# moire_v2.net
KiCad netlist of a schematic drawn in EAGLE
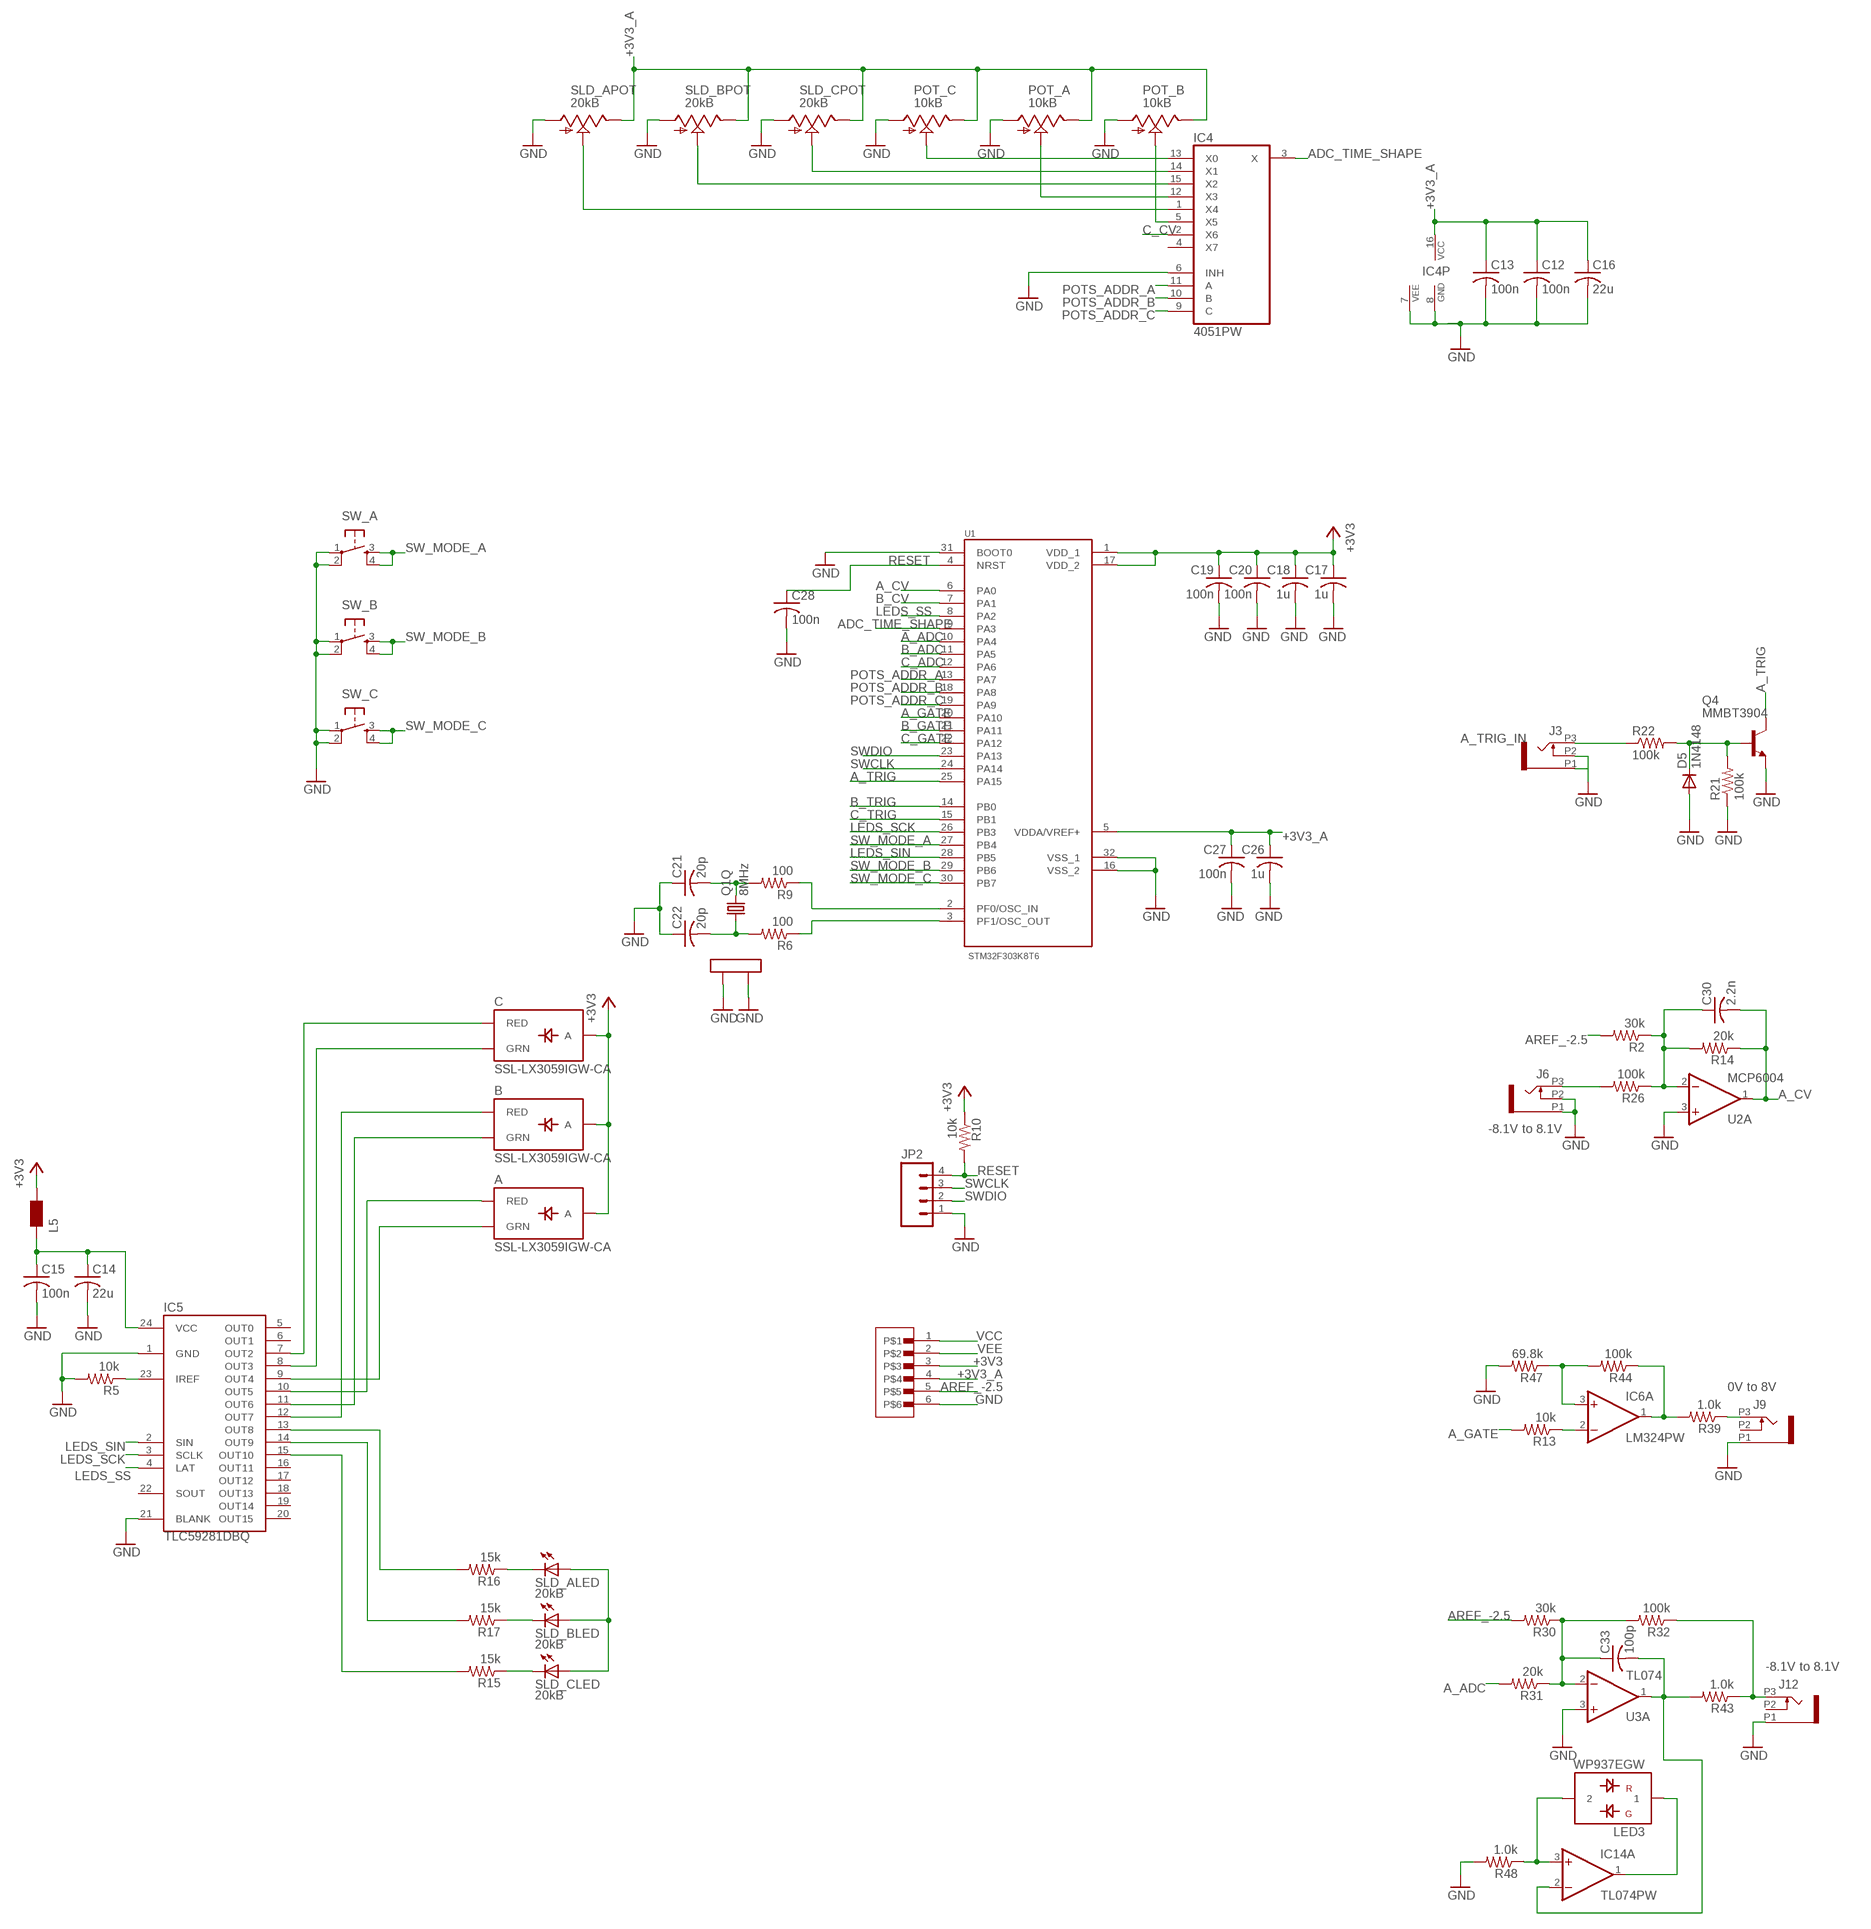
[diagram p0: schematic, sheet 1, part 1 of 2]
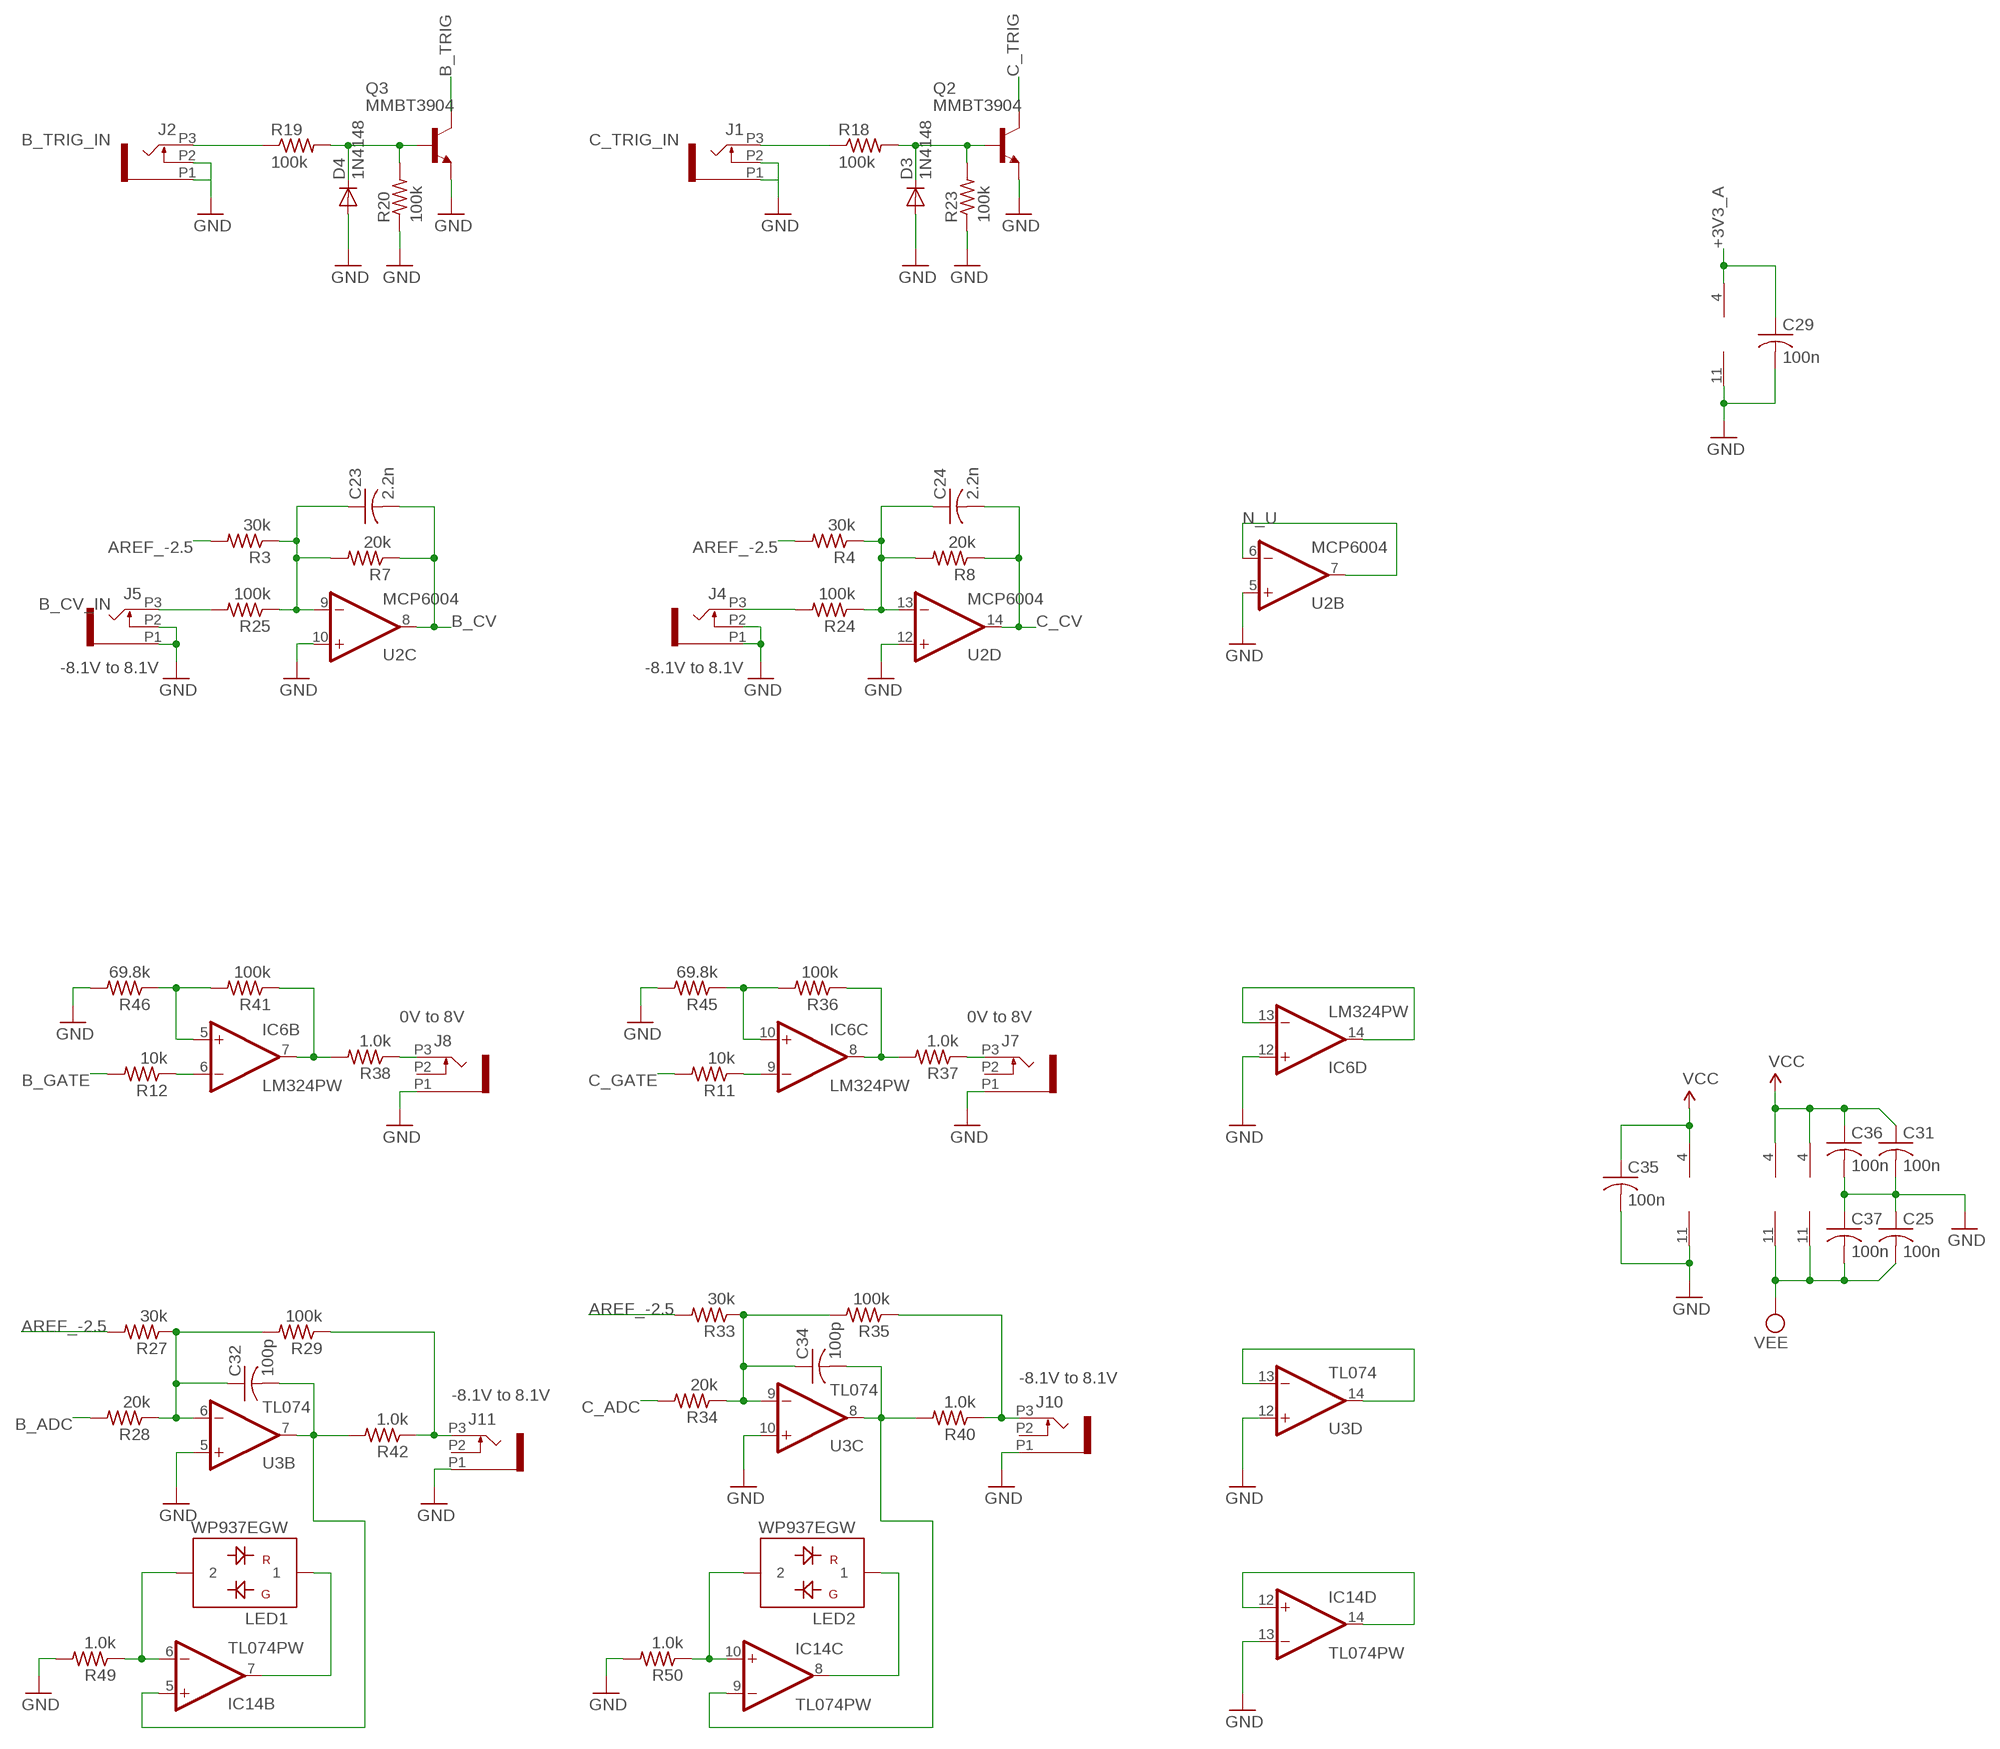
[diagram p1: schematic, sheet 1, part 2 of 2]
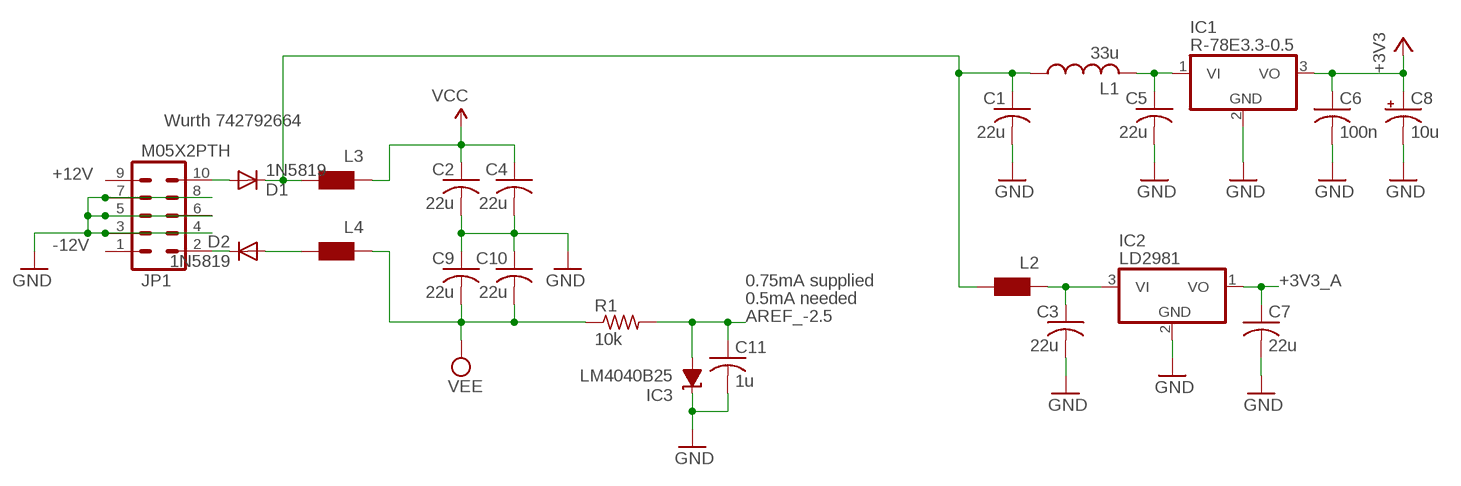
[diagram p2: schematic, sheet 2]

(export (version "E")
  (design (tool "Eeschema 10.0.6"))
  (components
    (comp (ref "A")
      (value "SSL-LX3059IGW-CA")
      (footprint "eagle-import:LED-BICOLOR-THROUGHHOLE-LUMEX")
      (libsource (lib "eagle-import") (part "LED-BICOLOR-THROUGHHOLE-CA"))
    )
    (comp (ref "B")
      (value "SSL-LX3059IGW-CA")
      (footprint "eagle-import:LED-BICOLOR-THROUGHHOLE-LUMEX")
      (libsource (lib "eagle-import") (part "LED-BICOLOR-THROUGHHOLE-CA"))
    )
    (comp (ref "C")
      (value "SSL-LX3059IGW-CA")
      (footprint "eagle-import:LED-BICOLOR-THROUGHHOLE-LUMEX")
      (libsource (lib "eagle-import") (part "LED-BICOLOR-THROUGHHOLE-CA"))
    )
    (comp (ref "C12")
      (value "100n")
      (footprint "eagle-import:RCL_C0603")
      (libsource (lib "eagle-import") (part "RCL_C-USC0603"))
    )
    (comp (ref "C13")
      (value "100n")
      (footprint "eagle-import:RCL_C0603")
      (libsource (lib "eagle-import") (part "RCL_C-USC0603"))
    )
    (comp (ref "C14")
      (value "22u")
      (footprint "eagle-import:RCL_C1206")
      (libsource (lib "eagle-import") (part "RCL_C-USC1206"))
    )
    (comp (ref "C15")
      (value "100n")
      (footprint "eagle-import:RCL_C0603")
      (libsource (lib "eagle-import") (part "RCL_C-USC0603"))
    )
    (comp (ref "C16")
      (value "22u")
      (footprint "eagle-import:RCL_C1206")
      (libsource (lib "eagle-import") (part "RCL_C-USC1206"))
    )
    (comp (ref "C17")
      (value "1u")
      (footprint "eagle-import:RCL_C0603")
      (libsource (lib "eagle-import") (part "RCL_C-USC0603"))
    )
    (comp (ref "C18")
      (value "1u")
      (footprint "eagle-import:RCL_C0603")
      (libsource (lib "eagle-import") (part "RCL_C-USC0603"))
    )
    (comp (ref "C19")
      (value "100n")
      (footprint "eagle-import:RCL_C0603")
      (libsource (lib "eagle-import") (part "RCL_C-USC0603"))
    )
    (comp (ref "C20")
      (value "100n")
      (footprint "eagle-import:RCL_C0603")
      (libsource (lib "eagle-import") (part "RCL_C-USC0603"))
    )
    (comp (ref "C21")
      (value "20p")
      (footprint "eagle-import:RCL_C0603")
      (libsource (lib "eagle-import") (part "RCL_C-USC0603"))
    )
    (comp (ref "C22")
      (value "20p")
      (footprint "eagle-import:RCL_C0603")
      (libsource (lib "eagle-import") (part "RCL_C-USC0603"))
    )
    (comp (ref "C23")
      (value "2.2n")
      (footprint "eagle-import:RCL_C0603")
      (libsource (lib "eagle-import") (part "RCL_C-USC0603"))
    )
    (comp (ref "C24")
      (value "2.2n")
      (footprint "eagle-import:RCL_C0603")
      (libsource (lib "eagle-import") (part "RCL_C-USC0603"))
    )
    (comp (ref "C25")
      (value "100n")
      (footprint "eagle-import:RCL_C0603")
      (libsource (lib "eagle-import") (part "RCL_C-USC0603"))
    )
    (comp (ref "C26")
      (value "1u")
      (footprint "eagle-import:RCL_C0603")
      (libsource (lib "eagle-import") (part "RCL_C-USC0603"))
    )
    (comp (ref "C27")
      (value "100n")
      (footprint "eagle-import:RCL_C0603")
      (libsource (lib "eagle-import") (part "RCL_C-USC0603"))
    )
    (comp (ref "C28")
      (value "100n")
      (footprint "eagle-import:RCL_C0603")
      (libsource (lib "eagle-import") (part "RCL_C-USC0603"))
    )
    (comp (ref "C29")
      (value "100n")
      (footprint "eagle-import:RCL_C0603")
      (libsource (lib "eagle-import") (part "RCL_C-USC0603"))
    )
    (comp (ref "C30")
      (value "2.2n")
      (footprint "eagle-import:RCL_C0603")
      (libsource (lib "eagle-import") (part "RCL_C-USC0603"))
    )
    (comp (ref "C31")
      (value "100n")
      (footprint "eagle-import:RCL_C0603")
      (libsource (lib "eagle-import") (part "RCL_C-USC0603"))
    )
    (comp (ref "C32")
      (value "100p")
      (footprint "eagle-import:RCL_C0603")
      (libsource (lib "eagle-import") (part "RCL_C-USC0603"))
    )
    (comp (ref "C33")
      (value "100p")
      (footprint "eagle-import:RCL_C0603")
      (libsource (lib "eagle-import") (part "RCL_C-USC0603"))
    )
    (comp (ref "C34")
      (value "100p")
      (footprint "eagle-import:RCL_C0603")
      (libsource (lib "eagle-import") (part "RCL_C-USC0603"))
    )
    (comp (ref "C35")
      (value "100n")
      (footprint "eagle-import:RCL_C0603")
      (libsource (lib "eagle-import") (part "RCL_C-USC0603"))
    )
    (comp (ref "C36")
      (value "100n")
      (footprint "eagle-import:RCL_C0603")
      (libsource (lib "eagle-import") (part "RCL_C-USC0603"))
    )
    (comp (ref "C37")
      (value "100n")
      (footprint "eagle-import:RCL_C0603")
      (libsource (lib "eagle-import") (part "RCL_C-USC0603"))
    )
    (comp (ref "D3")
      (value "1N4148")
      (footprint "eagle-import:DIODE_SOD523")
      (libsource (lib "eagle-import") (part "DIODE_DIODE-SOD523"))
    )
    (comp (ref "D4")
      (value "1N4148")
      (footprint "eagle-import:DIODE_SOD523")
      (libsource (lib "eagle-import") (part "DIODE_DIODE-SOD523"))
    )
    (comp (ref "D5")
      (value "1N4148")
      (footprint "eagle-import:DIODE_SOD523")
      (libsource (lib "eagle-import") (part "DIODE_DIODE-SOD523"))
    )
    (comp (ref "IC4")
      (value "4051PW")
      (footprint "eagle-import:TSSOP16_065")
      (libsource (lib "eagle-import") (part "4051PW"))
    )
    (comp (ref "IC5")
      (value "TLC59281DBQ")
      (footprint "eagle-import:TSSOP24_0635")
      (libsource (lib "eagle-import") (part "TLC59281DBQ"))
    )
    (comp (ref "IC6")
      (value "LM324PW")
      (footprint "eagle-import:TSSOP14_065")
      (libsource (lib "eagle-import") (part "og-linear_TL074PW"))
    )
    (comp (ref "IC14")
      (value "TL074PW")
      (footprint "eagle-import:TSSOP14_065")
      (libsource (lib "eagle-import") (part "TL074PW"))
    )
    (comp (ref "J1")
      (value "PJ301_THONKICONN6")
      (footprint "eagle-import:WQP_PJ_301M6")
      (libsource (lib "eagle-import") (part "PJ301_THONKICONN6"))
    )
    (comp (ref "J2")
      (value "PJ301_THONKICONN6")
      (footprint "eagle-import:WQP_PJ_301M6")
      (libsource (lib "eagle-import") (part "PJ301_THONKICONN6"))
    )
    (comp (ref "J3")
      (value "PJ301_THONKICONN6")
      (footprint "eagle-import:WQP_PJ_301M6")
      (libsource (lib "eagle-import") (part "PJ301_THONKICONN6"))
    )
    (comp (ref "J4")
      (value "PJ301_THONKICONN6")
      (footprint "eagle-import:WQP_PJ_301M6")
      (libsource (lib "eagle-import") (part "PJ301_THONKICONN6"))
    )
    (comp (ref "J5")
      (value "PJ301_THONKICONN6")
      (footprint "eagle-import:WQP_PJ_301M6")
      (libsource (lib "eagle-import") (part "PJ301_THONKICONN6"))
    )
    (comp (ref "J6")
      (value "PJ301_THONKICONN6")
      (footprint "eagle-import:WQP_PJ_301M6")
      (libsource (lib "eagle-import") (part "PJ301_THONKICONN6"))
    )
    (comp (ref "J7")
      (value "PJ301_THONKICONN6")
      (footprint "eagle-import:WQP_PJ_301M6")
      (libsource (lib "eagle-import") (part "PJ301_THONKICONN6"))
    )
    (comp (ref "J8")
      (value "PJ301_THONKICONN6")
      (footprint "eagle-import:WQP_PJ_301M6")
      (libsource (lib "eagle-import") (part "PJ301_THONKICONN6"))
    )
    (comp (ref "J9")
      (value "PJ301_THONKICONN6")
      (footprint "eagle-import:WQP_PJ_301M6")
      (libsource (lib "eagle-import") (part "PJ301_THONKICONN6"))
    )
    (comp (ref "J10")
      (value "PJ301_THONKICONN6")
      (footprint "eagle-import:WQP_PJ_301M6")
      (libsource (lib "eagle-import") (part "PJ301_THONKICONN6"))
    )
    (comp (ref "J11")
      (value "PJ301_THONKICONN6")
      (footprint "eagle-import:WQP_PJ_301M6")
      (libsource (lib "eagle-import") (part "PJ301_THONKICONN6"))
    )
    (comp (ref "J12")
      (value "PJ301_THONKICONN6")
      (footprint "eagle-import:WQP_PJ_301M6")
      (libsource (lib "eagle-import") (part "PJ301_THONKICONN6"))
    )
    (comp (ref "JP2")
      (value "M04PTH")
      (footprint "eagle-import:1X04")
      (libsource (lib "eagle-import") (part "M04PTH"))
    )
    (comp (ref "L5")
      (value "WE-CBF_0603")
      (footprint "eagle-import:0603")
      (libsource (lib "eagle-import") (part "WE-CBF_0603"))
    )
    (comp (ref "LED1")
      (value "WP937EGW")
      (footprint "eagle-import:LED3MM")
      (libsource (lib "eagle-import") (part "LED-BICOLOR-SHARED-THROUGHHOLE"))
    )
    (comp (ref "LED2")
      (value "WP937EGW")
      (footprint "eagle-import:LED3MM")
      (libsource (lib "eagle-import") (part "LED-BICOLOR-SHARED-THROUGHHOLE"))
    )
    (comp (ref "LED3")
      (value "WP937EGW")
      (footprint "eagle-import:LED3MM")
      (libsource (lib "eagle-import") (part "LED-BICOLOR-SHARED-THROUGHHOLE"))
    )
    (comp (ref "POT_A")
      (value "10kB")
      (footprint "eagle-import:ALPS_POT_VERTICAL")
      (libsource (lib "eagle-import") (part "POT_USVERTICAL"))
    )
    (comp (ref "POT_B")
      (value "10kB")
      (footprint "eagle-import:ALPS_POT_VERTICAL")
      (libsource (lib "eagle-import") (part "POT_USVERTICAL"))
    )
    (comp (ref "POT_C")
      (value "10kB")
      (footprint "eagle-import:ALPS_POT_VERTICAL")
      (libsource (lib "eagle-import") (part "POT_USVERTICAL"))
    )
    (comp (ref "Q1")
      (value "8MHz")
      (footprint "eagle-import:CTS406")
      (libsource (lib "eagle-import") (part "CRYSTAL"))
    )
    (comp (ref "Q2")
      (value "MMBT3904")
      (footprint "eagle-import:SOT23-BEC")
      (libsource (lib "eagle-import") (part "-NPN-SOT23-BECMMBT3904LT1"))
    )
    (comp (ref "Q3")
      (value "MMBT3904")
      (footprint "eagle-import:SOT23-BEC")
      (libsource (lib "eagle-import") (part "-NPN-SOT23-BECMMBT3904LT1"))
    )
    (comp (ref "Q4")
      (value "MMBT3904")
      (footprint "eagle-import:SOT23-BEC")
      (libsource (lib "eagle-import") (part "-NPN-SOT23-BECMMBT3904LT1"))
    )
    (comp (ref "R2")
      (value "30k")
      (footprint "eagle-import:RCL_R0603")
      (libsource (lib "eagle-import") (part "RCL_R-US_R0603"))
    )
    (comp (ref "R3")
      (value "30k")
      (footprint "eagle-import:RCL_R0603")
      (libsource (lib "eagle-import") (part "RCL_R-US_R0603"))
    )
    (comp (ref "R4")
      (value "30k")
      (footprint "eagle-import:RCL_R0603")
      (libsource (lib "eagle-import") (part "RCL_R-US_R0603"))
    )
    (comp (ref "R5")
      (value "10k")
      (footprint "eagle-import:RCL_R0603")
      (libsource (lib "eagle-import") (part "RCL_R-US_R0603"))
    )
    (comp (ref "R6")
      (value "100")
      (footprint "eagle-import:RCL_R0603")
      (libsource (lib "eagle-import") (part "RCL_R-US_R0603"))
    )
    (comp (ref "R7")
      (value "20k")
      (footprint "eagle-import:RCL_R0603")
      (libsource (lib "eagle-import") (part "RCL_R-US_R0603"))
    )
    (comp (ref "R8")
      (value "20k")
      (footprint "eagle-import:RCL_R0603")
      (libsource (lib "eagle-import") (part "RCL_R-US_R0603"))
    )
    (comp (ref "R9")
      (value "100")
      (footprint "eagle-import:RCL_R0603")
      (libsource (lib "eagle-import") (part "RCL_R-US_R0603"))
    )
    (comp (ref "R10")
      (value "10k")
      (footprint "eagle-import:RCL_R0603")
      (libsource (lib "eagle-import") (part "RCL_R-US_R0603"))
    )
    (comp (ref "R11")
      (value "10k")
      (footprint "eagle-import:RCL_R0603")
      (libsource (lib "eagle-import") (part "RCL_R-US_R0603"))
    )
    (comp (ref "R12")
      (value "10k")
      (footprint "eagle-import:RCL_R0603")
      (libsource (lib "eagle-import") (part "RCL_R-US_R0603"))
    )
    (comp (ref "R13")
      (value "10k")
      (footprint "eagle-import:RCL_R0603")
      (libsource (lib "eagle-import") (part "RCL_R-US_R0603"))
    )
    (comp (ref "R14")
      (value "20k")
      (footprint "eagle-import:RCL_R0603")
      (libsource (lib "eagle-import") (part "RCL_R-US_R0603"))
    )
    (comp (ref "R15")
      (value "15k")
      (footprint "eagle-import:RCL_R0603")
      (libsource (lib "eagle-import") (part "RCL_R-US_R0603"))
    )
    (comp (ref "R16")
      (value "15k")
      (footprint "eagle-import:RCL_R0603")
      (libsource (lib "eagle-import") (part "RCL_R-US_R0603"))
    )
    (comp (ref "R17")
      (value "15k")
      (footprint "eagle-import:RCL_R0603")
      (libsource (lib "eagle-import") (part "RCL_R-US_R0603"))
    )
    (comp (ref "R18")
      (value "100k")
      (footprint "eagle-import:RCL_R0603")
      (libsource (lib "eagle-import") (part "RCL_R-US_R0603"))
    )
    (comp (ref "R19")
      (value "100k")
      (footprint "eagle-import:RCL_R0603")
      (libsource (lib "eagle-import") (part "RCL_R-US_R0603"))
    )
    (comp (ref "R20")
      (value "100k")
      (footprint "eagle-import:RCL_R0603")
      (libsource (lib "eagle-import") (part "RCL_R-US_R0603"))
    )
    (comp (ref "R21")
      (value "100k")
      (footprint "eagle-import:RCL_R0603")
      (libsource (lib "eagle-import") (part "RCL_R-US_R0603"))
    )
    (comp (ref "R22")
      (value "100k")
      (footprint "eagle-import:RCL_R0603")
      (libsource (lib "eagle-import") (part "RCL_R-US_R0603"))
    )
    (comp (ref "R23")
      (value "100k")
      (footprint "eagle-import:RCL_R0603")
      (libsource (lib "eagle-import") (part "RCL_R-US_R0603"))
    )
    (comp (ref "R24")
      (value "100k")
      (footprint "eagle-import:RCL_R0603")
      (libsource (lib "eagle-import") (part "RCL_R-US_R0603"))
    )
    (comp (ref "R25")
      (value "100k")
      (footprint "eagle-import:RCL_R0603")
      (libsource (lib "eagle-import") (part "RCL_R-US_R0603"))
    )
    (comp (ref "R26")
      (value "100k")
      (footprint "eagle-import:RCL_R0603")
      (libsource (lib "eagle-import") (part "RCL_R-US_R0603"))
    )
    (comp (ref "R27")
      (value "30k")
      (footprint "eagle-import:RCL_R0603")
      (libsource (lib "eagle-import") (part "RCL_R-US_R0603"))
    )
    (comp (ref "R28")
      (value "20k")
      (footprint "eagle-import:RCL_R0603")
      (libsource (lib "eagle-import") (part "RCL_R-US_R0603"))
    )
    (comp (ref "R29")
      (value "100k")
      (footprint "eagle-import:RCL_R0603")
      (libsource (lib "eagle-import") (part "RCL_R-US_R0603"))
    )
    (comp (ref "R30")
      (value "30k")
      (footprint "eagle-import:RCL_R0603")
      (libsource (lib "eagle-import") (part "RCL_R-US_R0603"))
    )
    (comp (ref "R31")
      (value "20k")
      (footprint "eagle-import:RCL_R0603")
      (libsource (lib "eagle-import") (part "RCL_R-US_R0603"))
    )
    (comp (ref "R32")
      (value "100k")
      (footprint "eagle-import:RCL_R0603")
      (libsource (lib "eagle-import") (part "RCL_R-US_R0603"))
    )
    (comp (ref "R33")
      (value "30k")
      (footprint "eagle-import:RCL_R0603")
      (libsource (lib "eagle-import") (part "RCL_R-US_R0603"))
    )
    (comp (ref "R34")
      (value "20k")
      (footprint "eagle-import:RCL_R0603")
      (libsource (lib "eagle-import") (part "RCL_R-US_R0603"))
    )
    (comp (ref "R35")
      (value "100k")
      (footprint "eagle-import:RCL_R0603")
      (libsource (lib "eagle-import") (part "RCL_R-US_R0603"))
    )
    (comp (ref "R36")
      (value "100k")
      (footprint "eagle-import:RCL_R0603")
      (libsource (lib "eagle-import") (part "RCL_R-US_R0603"))
    )
    (comp (ref "R37")
      (value "1.0k")
      (footprint "eagle-import:RCL_R0603")
      (libsource (lib "eagle-import") (part "RCL_R-US_R0603"))
    )
    (comp (ref "R38")
      (value "1.0k")
      (footprint "eagle-import:RCL_R0603")
      (libsource (lib "eagle-import") (part "RCL_R-US_R0603"))
    )
    (comp (ref "R39")
      (value "1.0k")
      (footprint "eagle-import:RCL_R0603")
      (libsource (lib "eagle-import") (part "RCL_R-US_R0603"))
    )
    (comp (ref "R40")
      (value "1.0k")
      (footprint "eagle-import:RCL_R0603")
      (libsource (lib "eagle-import") (part "RCL_R-US_R0603"))
    )
    (comp (ref "R41")
      (value "100k")
      (footprint "eagle-import:RCL_R0603")
      (libsource (lib "eagle-import") (part "RCL_R-US_R0603"))
    )
    (comp (ref "R42")
      (value "1.0k")
      (footprint "eagle-import:RCL_R0603")
      (libsource (lib "eagle-import") (part "RCL_R-US_R0603"))
    )
    (comp (ref "R43")
      (value "1.0k")
      (footprint "eagle-import:RCL_R0603")
      (libsource (lib "eagle-import") (part "RCL_R-US_R0603"))
    )
    (comp (ref "R44")
      (value "100k")
      (footprint "eagle-import:RCL_R0603")
      (libsource (lib "eagle-import") (part "RCL_R-US_R0603"))
    )
    (comp (ref "R45")
      (value "69.8k")
      (footprint "eagle-import:RCL_R0603")
      (libsource (lib "eagle-import") (part "RCL_R-US_R0603"))
    )
    (comp (ref "R46")
      (value "69.8k")
      (footprint "eagle-import:RCL_R0603")
      (libsource (lib "eagle-import") (part "RCL_R-US_R0603"))
    )
    (comp (ref "R47")
      (value "69.8k")
      (footprint "eagle-import:RCL_R0603")
      (libsource (lib "eagle-import") (part "RCL_R-US_R0603"))
    )
    (comp (ref "R48")
      (value "1.0k")
      (footprint "eagle-import:RCL_R0603")
      (libsource (lib "eagle-import") (part "RCL_R-US_R0603"))
    )
    (comp (ref "R49")
      (value "1.0k")
      (footprint "eagle-import:RCL_R0603")
      (libsource (lib "eagle-import") (part "RCL_R-US_R0603"))
    )
    (comp (ref "R50")
      (value "1.0k")
      (footprint "eagle-import:RCL_R0603")
      (libsource (lib "eagle-import") (part "RCL_R-US_R0603"))
    )
    (comp (ref "SLD_A")
      (value "20kB")
      (footprint "eagle-import:BOURNS_SLIDER")
      (libsource (lib "eagle-import") (part "BOURNS_SLIDER"))
    )
    (comp (ref "SLD_B")
      (value "20kB")
      (footprint "eagle-import:BOURNS_SLIDER")
      (libsource (lib "eagle-import") (part "BOURNS_SLIDER"))
    )
    (comp (ref "SLD_C")
      (value "20kB")
      (footprint "eagle-import:BOURNS_SLIDER")
      (libsource (lib "eagle-import") (part "BOURNS_SLIDER"))
    )
    (comp (ref "SW_A")
      (value "TAC_SWITCHPTH")
      (footprint "eagle-import:TACTILE-PTH")
      (libsource (lib "eagle-import") (part "TAC_SWITCHPTH"))
    )
    (comp (ref "SW_B")
      (value "TAC_SWITCHPTH")
      (footprint "eagle-import:TACTILE-PTH")
      (libsource (lib "eagle-import") (part "TAC_SWITCHPTH"))
    )
    (comp (ref "SW_C")
      (value "TAC_SWITCHPTH")
      (footprint "eagle-import:TACTILE-PTH")
      (libsource (lib "eagle-import") (part "TAC_SWITCHPTH"))
    )
    (comp (ref "U$1")
      (value "1X6-SMD-TESTPAD")
      (footprint "eagle-import:6X1-SMD-TESTPAD")
      (libsource (lib "eagle-import") (part "1X6-SMD-TESTPAD"))
    )
    (comp (ref "U1")
      (value "STM32F303K8T6")
      (footprint "eagle-import:QFP80P900X900X160-32N")
      (fields (field (name "MF") "STMicroelectronics"))
      (libsource (lib "eagle-import") (part "STM32F303K8T6"))
    )
    (comp (ref "U2")
      (value "MCP6004")
      (footprint "eagle-import:SO14")
      (libsource (lib "eagle-import") (part "MCP6004_SMD"))
    )
    (comp (ref "U3")
      (value "TL074")
      (footprint "eagle-import:SO14")
      (libsource (lib "eagle-import") (part "TL074_SMD"))
    )
    (comp (ref "C1")
      (value "22u")
      (footprint "eagle-import:RCL_C1206")
      (libsource (lib "eagle-import") (part "RCL_C-USC1206"))
    )
    (comp (ref "C2")
      (value "22u")
      (footprint "eagle-import:RCL_C1206")
      (libsource (lib "eagle-import") (part "RCL_C-USC1206"))
    )
    (comp (ref "C3")
      (value "22u")
      (footprint "eagle-import:RCL_C1206")
      (libsource (lib "eagle-import") (part "RCL_C-USC1206"))
    )
    (comp (ref "C4")
      (value "22u")
      (footprint "eagle-import:RCL_C1206")
      (libsource (lib "eagle-import") (part "RCL_C-USC1206"))
    )
    (comp (ref "C5")
      (value "22u")
      (footprint "eagle-import:RCL_C1206")
      (libsource (lib "eagle-import") (part "RCL_C-USC1206"))
    )
    (comp (ref "C6")
      (value "100n")
      (footprint "eagle-import:RCL_C0603")
      (libsource (lib "eagle-import") (part "RCL_C-USC0603"))
    )
    (comp (ref "C7")
      (value "22u")
      (footprint "eagle-import:RCL_C1206")
      (libsource (lib "eagle-import") (part "RCL_C-USC1206"))
    )
    (comp (ref "C8")
      (value "10u")
      (footprint "eagle-import:RCL_PANASONIC_A")
      (libsource (lib "eagle-import") (part "RCL_CPOL-USA"))
    )
    (comp (ref "C9")
      (value "22u")
      (footprint "eagle-import:RCL_C1206")
      (libsource (lib "eagle-import") (part "RCL_C-USC1206"))
    )
    (comp (ref "C10")
      (value "22u")
      (footprint "eagle-import:RCL_C1206")
      (libsource (lib "eagle-import") (part "RCL_C-USC1206"))
    )
    (comp (ref "C11")
      (value "1u")
      (footprint "eagle-import:RCL_C0603")
      (libsource (lib "eagle-import") (part "RCL_C-USC0603"))
    )
    (comp (ref "D1")
      (value "1N5819")
      (footprint "eagle-import:DIODE_SOD123")
      (libsource (lib "eagle-import") (part "DIODE_DIODE-SOD123"))
    )
    (comp (ref "D2")
      (value "1N5819")
      (footprint "eagle-import:DIODE_SOD123")
      (libsource (lib "eagle-import") (part "DIODE_DIODE-SOD123"))
    )
    (comp (ref "IC1")
      (value "R-78E3.3-0.5")
      (footprint "eagle-import:WE78")
      (libsource (lib "eagle-import") (part "WE173950378"))
    )
    (comp (ref "IC2")
      (value "LD2981")
      (footprint "eagle-import:SOT89")
      (libsource (lib "eagle-import") (part "LD2981ABU"))
    )
    (comp (ref "IC3")
      (value "LM4040B25")
      (footprint "eagle-import:DBZ_R-PDSO-G3")
      (libsource (lib "eagle-import") (part "LM4041DBZB12"))
    )
    (comp (ref "JP1")
      (value "M05X2PTH")
      (footprint "eagle-import:2X5-PTH")
      (libsource (lib "eagle-import") (part "M05X2PTH"))
    )
    (comp (ref "L1")
      (value "33u")
      (footprint "eagle-import:L2012C")
      (libsource (lib "eagle-import") (part "L-USL2012C"))
    )
    (comp (ref "L2")
      (value "WE-CBF_0603")
      (footprint "eagle-import:0603")
      (libsource (lib "eagle-import") (part "WE-CBF_0603"))
    )
    (comp (ref "L3")
      (value "WE-CBF_0603")
      (footprint "eagle-import:0603")
      (libsource (lib "eagle-import") (part "WE-CBF_0603"))
    )
    (comp (ref "L4")
      (value "WE-CBF_0603")
      (footprint "eagle-import:0603")
      (libsource (lib "eagle-import") (part "WE-CBF_0603"))
    )
    (comp (ref "R1")
      (value "10k")
      (footprint "eagle-import:RCL_R0603")
      (libsource (lib "eagle-import") (part "RCL_R-US_R0603"))
    )
  )
  (nets
    (net (code "1") (name "+3V3") (class "Default")
      (node (ref "A") (pin "A") (pinfunction "A_A") (pintype "bidirectional"))
      (node (ref "B") (pin "A") (pinfunction "A_A") (pintype "bidirectional"))
      (node (ref "C") (pin "A") (pinfunction "A_A") (pintype "bidirectional"))
      (node (ref "C17") (pin "1") (pinfunction "1_1") (pintype "passive"))
      (node (ref "C18") (pin "1") (pinfunction "1_1") (pintype "passive"))
      (node (ref "C19") (pin "1") (pinfunction "1_1") (pintype "passive"))
      (node (ref "C20") (pin "1") (pinfunction "1_1") (pintype "passive"))
      (node (ref "C6") (pin "1") (pinfunction "1_1") (pintype "passive"))
      (node (ref "C8") (pin "+") (pinfunction "+_+") (pintype "passive"))
      (node (ref "IC1") (pin "3") (pinfunction "VO_3") (pintype "passive"))
      (node (ref "L5") (pin "2") (pinfunction "2_2") (pintype "passive"))
      (node (ref "R10") (pin "1") (pinfunction "1_1") (pintype "passive"))
      (node (ref "U$1") (pin "3") (pinfunction "P$3_3") (pintype "bidirectional"))
      (node (ref "U1") (pin "1") (pinfunction "VDD_1_1") (pintype "power_in"))
      (node (ref "U1") (pin "17") (pinfunction "VDD_2_17") (pintype "power_in"))
    )
    (net (code "2") (name "+3V3_A") (class "Default")
      (node (ref "C12") (pin "1") (pinfunction "1_1") (pintype "passive"))
      (node (ref "C13") (pin "1") (pinfunction "1_1") (pintype "passive"))
      (node (ref "C16") (pin "1") (pinfunction "1_1") (pintype "passive"))
      (node (ref "C26") (pin "1") (pinfunction "1_1") (pintype "passive"))
      (node (ref "C27") (pin "1") (pinfunction "1_1") (pintype "passive"))
      (node (ref "C29") (pin "1") (pinfunction "1_1") (pintype "passive"))
      (node (ref "C7") (pin "1") (pinfunction "1_1") (pintype "passive"))
      (node (ref "IC2") (pin "1") (pinfunction "VO_1") (pintype "passive"))
      (node (ref "IC4") (pin "16") (pinfunction "VCC_16") (pintype "power_in"))
      (node (ref "POT_A") (pin "P$1") (pinfunction "E_P$1") (pintype "passive"))
      (node (ref "POT_B") (pin "P$1") (pinfunction "E_P$1") (pintype "passive"))
      (node (ref "POT_C") (pin "P$1") (pinfunction "E_P$1") (pintype "passive"))
      (node (ref "SLD_A") (pin "3") (pinfunction "E_3") (pintype "passive"))
      (node (ref "SLD_B") (pin "3") (pinfunction "E_3") (pintype "passive"))
      (node (ref "SLD_C") (pin "3") (pinfunction "E_3") (pintype "passive"))
      (node (ref "U$1") (pin "4") (pinfunction "P$4_4") (pintype "bidirectional"))
      (node (ref "U1") (pin "5") (pinfunction "VDDA/VREF+_5") (pintype "power_in"))
      (node (ref "U2") (pin "4") (pinfunction "V+_4") (pintype "power_in"))
    )
    (net (code "3") (name "+12V") (class "Default")
      (node (ref "D1") (pin "A") (pinfunction "A_A") (pintype "passive"))
      (node (ref "JP1") (pin "10") (pinfunction "10_10") (pintype "passive"))
      (node (ref "JP1") (pin "9") (pinfunction "9_9") (pintype "passive"))
    )
    (net (code "4") (name "-12V") (class "Default")
      (node (ref "D2") (pin "C") (pinfunction "C_C") (pintype "passive"))
      (node (ref "JP1") (pin "1") (pinfunction "1_1") (pintype "passive"))
      (node (ref "JP1") (pin "2") (pinfunction "2_2") (pintype "passive"))
    )
    (net (code "5") (name "ADC_TIME_SHAPE") (class "Default")
      (node (ref "IC4") (pin "3") (pinfunction "X_3") (pintype "bidirectional"))
      (node (ref "U1") (pin "9") (pinfunction "PA3_9") (pintype "bidirectional"))
    )
    (net (code "6") (name "AREF_-2.5") (class "Default")
      (node (ref "C11") (pin "1") (pinfunction "1_1") (pintype "passive"))
      (node (ref "IC3") (pin "2") (pinfunction "A_2") (pintype "passive"))
      (node (ref "R1") (pin "2") (pinfunction "2_2") (pintype "passive"))
      (node (ref "R2") (pin "2") (pinfunction "2_2") (pintype "passive"))
      (node (ref "R27") (pin "2") (pinfunction "2_2") (pintype "passive"))
      (node (ref "R3") (pin "2") (pinfunction "2_2") (pintype "passive"))
      (node (ref "R30") (pin "2") (pinfunction "2_2") (pintype "passive"))
      (node (ref "R33") (pin "2") (pinfunction "2_2") (pintype "passive"))
      (node (ref "R4") (pin "2") (pinfunction "2_2") (pintype "passive"))
      (node (ref "U$1") (pin "5") (pinfunction "P$5_5") (pintype "bidirectional"))
    )
    (net (code "7") (name "A_ADC") (class "Default")
      (node (ref "R31") (pin "2") (pinfunction "2_2") (pintype "passive"))
      (node (ref "U1") (pin "10") (pinfunction "PA4_10") (pintype "bidirectional"))
    )
    (net (code "8") (name "A_CV") (class "Default")
      (node (ref "C30") (pin "2") (pinfunction "2_2") (pintype "passive"))
      (node (ref "R14") (pin "1") (pinfunction "1_1") (pintype "passive"))
      (node (ref "U1") (pin "6") (pinfunction "PA0_6") (pintype "bidirectional"))
      (node (ref "U2") (pin "1") (pinfunction "OUT_1") (pintype "output"))
    )
    (net (code "9") (name "A_GATE") (class "Default")
      (node (ref "R13") (pin "2") (pinfunction "2_2") (pintype "passive"))
      (node (ref "U1") (pin "20") (pinfunction "PA10_20") (pintype "bidirectional"))
    )
    (net (code "10") (name "A_TRIG") (class "Default")
      (node (ref "Q4") (pin "C") (pinfunction "C_C") (pintype "passive"))
      (node (ref "U1") (pin "25") (pinfunction "PA15_25") (pintype "bidirectional"))
    )
    (net (code "11") (name "A_TRIG_IN") (class "Default")
      (node (ref "J3") (pin "P3") (pinfunction "3_P3") (pintype "passive"))
      (node (ref "R22") (pin "1") (pinfunction "1_1") (pintype "passive"))
    )
    (net (code "12") (name "B_ADC") (class "Default")
      (node (ref "R28") (pin "2") (pinfunction "2_2") (pintype "passive"))
      (node (ref "U1") (pin "11") (pinfunction "PA5_11") (pintype "bidirectional"))
    )
    (net (code "13") (name "B_CV") (class "Default")
      (node (ref "C23") (pin "2") (pinfunction "2_2") (pintype "passive"))
      (node (ref "R7") (pin "1") (pinfunction "1_1") (pintype "passive"))
      (node (ref "U1") (pin "7") (pinfunction "PA1_7") (pintype "bidirectional"))
      (node (ref "U2") (pin "8") (pinfunction "OUT_8") (pintype "output"))
    )
    (net (code "14") (name "B_CV_IN") (class "Default")
      (node (ref "J5") (pin "P3") (pinfunction "3_P3") (pintype "passive"))
      (node (ref "R25") (pin "2") (pinfunction "2_2") (pintype "passive"))
    )
    (net (code "15") (name "B_GATE") (class "Default")
      (node (ref "R12") (pin "2") (pinfunction "2_2") (pintype "passive"))
      (node (ref "U1") (pin "21") (pinfunction "PA11_21") (pintype "bidirectional"))
    )
    (net (code "16") (name "B_TRIG") (class "Default")
      (node (ref "Q3") (pin "C") (pinfunction "C_C") (pintype "passive"))
      (node (ref "U1") (pin "14") (pinfunction "PB0_14") (pintype "bidirectional"))
    )
    (net (code "17") (name "B_TRIG_IN") (class "Default")
      (node (ref "J2") (pin "P3") (pinfunction "3_P3") (pintype "passive"))
      (node (ref "R19") (pin "1") (pinfunction "1_1") (pintype "passive"))
    )
    (net (code "18") (name "C_ADC") (class "Default")
      (node (ref "R34") (pin "2") (pinfunction "2_2") (pintype "passive"))
      (node (ref "U1") (pin "12") (pinfunction "PA6_12") (pintype "bidirectional"))
    )
    (net (code "19") (name "C_CV") (class "Default")
      (node (ref "C24") (pin "2") (pinfunction "2_2") (pintype "passive"))
      (node (ref "IC4") (pin "2") (pinfunction "X6_2") (pintype "bidirectional"))
      (node (ref "R8") (pin "1") (pinfunction "1_1") (pintype "passive"))
      (node (ref "U2") (pin "14") (pinfunction "OUT_14") (pintype "output"))
    )
    (net (code "20") (name "C_GATE") (class "Default")
      (node (ref "R11") (pin "2") (pinfunction "2_2") (pintype "passive"))
      (node (ref "U1") (pin "22") (pinfunction "PA12_22") (pintype "bidirectional"))
    )
    (net (code "21") (name "C_TRIG") (class "Default")
      (node (ref "Q2") (pin "C") (pinfunction "C_C") (pintype "passive"))
      (node (ref "U1") (pin "15") (pinfunction "PB1_15") (pintype "bidirectional"))
    )
    (net (code "22") (name "C_TRIG_IN") (class "Default")
      (node (ref "J1") (pin "P3") (pinfunction "3_P3") (pintype "passive"))
      (node (ref "R18") (pin "1") (pinfunction "1_1") (pintype "passive"))
    )
    (net (code "23") (name "GND") (class "Default")
      (node (ref "C1") (pin "2") (pinfunction "2_2") (pintype "passive"))
      (node (ref "C10") (pin "1") (pinfunction "1_1") (pintype "passive"))
      (node (ref "C11") (pin "2") (pinfunction "2_2") (pintype "passive"))
      (node (ref "C12") (pin "2") (pinfunction "2_2") (pintype "passive"))
      (node (ref "C13") (pin "2") (pinfunction "2_2") (pintype "passive"))
      (node (ref "C14") (pin "2") (pinfunction "2_2") (pintype "passive"))
      (node (ref "C15") (pin "2") (pinfunction "2_2") (pintype "passive"))
      (node (ref "C16") (pin "2") (pinfunction "2_2") (pintype "passive"))
      (node (ref "C17") (pin "2") (pinfunction "2_2") (pintype "passive"))
      (node (ref "C18") (pin "2") (pinfunction "2_2") (pintype "passive"))
      (node (ref "C19") (pin "2") (pinfunction "2_2") (pintype "passive"))
      (node (ref "C2") (pin "2") (pinfunction "2_2") (pintype "passive"))
      (node (ref "C20") (pin "2") (pinfunction "2_2") (pintype "passive"))
      (node (ref "C21") (pin "1") (pinfunction "1_1") (pintype "passive"))
      (node (ref "C22") (pin "1") (pinfunction "1_1") (pintype "passive"))
      (node (ref "C25") (pin "1") (pinfunction "1_1") (pintype "passive"))
      (node (ref "C26") (pin "2") (pinfunction "2_2") (pintype "passive"))
      (node (ref "C27") (pin "2") (pinfunction "2_2") (pintype "passive"))
      (node (ref "C28") (pin "2") (pinfunction "2_2") (pintype "passive"))
      (node (ref "C29") (pin "2") (pinfunction "2_2") (pintype "passive"))
      (node (ref "C3") (pin "2") (pinfunction "2_2") (pintype "passive"))
      (node (ref "C31") (pin "2") (pinfunction "2_2") (pintype "passive"))
      (node (ref "C35") (pin "2") (pinfunction "2_2") (pintype "passive"))
      (node (ref "C36") (pin "2") (pinfunction "2_2") (pintype "passive"))
      (node (ref "C37") (pin "1") (pinfunction "1_1") (pintype "passive"))
      (node (ref "C4") (pin "2") (pinfunction "2_2") (pintype "passive"))
      (node (ref "C5") (pin "2") (pinfunction "2_2") (pintype "passive"))
      (node (ref "C6") (pin "2") (pinfunction "2_2") (pintype "passive"))
      (node (ref "C7") (pin "2") (pinfunction "2_2") (pintype "passive"))
      (node (ref "C8") (pin "-") (pinfunction "-_-") (pintype "passive"))
      (node (ref "C9") (pin "1") (pinfunction "1_1") (pintype "passive"))
      (node (ref "D3") (pin "A") (pinfunction "A_A") (pintype "passive"))
      (node (ref "D4") (pin "A") (pinfunction "A_A") (pintype "passive"))
      (node (ref "D5") (pin "A") (pinfunction "A_A") (pintype "passive"))
      (node (ref "IC1") (pin "2") (pinfunction "GND_2") (pintype "passive"))
      (node (ref "IC14") (pin "13") (pinfunction "-IN_13") (pintype "input"))
      (node (ref "IC2") (pin "2") (pinfunction "GND_2") (pintype "passive"))
      (node (ref "IC3") (pin "1") (pinfunction "C_1") (pintype "passive"))
      (node (ref "IC4") (pin "6") (pinfunction "INH_6") (pintype "input"))
      (node (ref "IC4") (pin "7") (pinfunction "VEE_7") (pintype "power_in"))
      (node (ref "IC4") (pin "8") (pinfunction "GND_8") (pintype "power_in"))
      (node (ref "IC5") (pin "1") (pinfunction "GND_1") (pintype "bidirectional"))
      (node (ref "IC5") (pin "21") (pinfunction "BLANK_21") (pintype "bidirectional"))
      (node (ref "IC6") (pin "11") (pinfunction "V-_11") (pintype "power_in"))
      (node (ref "IC6") (pin "12") (pinfunction "+IN_12") (pintype "input"))
      (node (ref "J1") (pin "P1") (pinfunction "1_P1") (pintype "passive"))
      (node (ref "J1") (pin "P2") (pinfunction "2_P2") (pintype "passive"))
      (node (ref "J10") (pin "P1") (pinfunction "1_P1") (pintype "passive"))
      (node (ref "J11") (pin "P1") (pinfunction "1_P1") (pintype "passive"))
      (node (ref "J12") (pin "P1") (pinfunction "1_P1") (pintype "passive"))
      (node (ref "J2") (pin "P1") (pinfunction "1_P1") (pintype "passive"))
      (node (ref "J2") (pin "P2") (pinfunction "2_P2") (pintype "passive"))
      (node (ref "J3") (pin "P1") (pinfunction "1_P1") (pintype "passive"))
      (node (ref "J3") (pin "P2") (pinfunction "2_P2") (pintype "passive"))
      (node (ref "J4") (pin "P1") (pinfunction "1_P1") (pintype "passive"))
      (node (ref "J4") (pin "P2") (pinfunction "2_P2") (pintype "passive"))
      (node (ref "J5") (pin "P1") (pinfunction "1_P1") (pintype "passive"))
      (node (ref "J5") (pin "P2") (pinfunction "2_P2") (pintype "passive"))
      (node (ref "J6") (pin "P1") (pinfunction "1_P1") (pintype "passive"))
      (node (ref "J6") (pin "P2") (pinfunction "2_P2") (pintype "passive"))
      (node (ref "J7") (pin "P1") (pinfunction "1_P1") (pintype "passive"))
      (node (ref "J8") (pin "P1") (pinfunction "1_P1") (pintype "passive"))
      (node (ref "J9") (pin "P1") (pinfunction "1_P1") (pintype "passive"))
      (node (ref "JP1") (pin "3") (pinfunction "3_3") (pintype "passive"))
      (node (ref "JP1") (pin "4") (pinfunction "4_4") (pintype "passive"))
      (node (ref "JP1") (pin "5") (pinfunction "5_5") (pintype "passive"))
      (node (ref "JP1") (pin "6") (pinfunction "6_6") (pintype "passive"))
      (node (ref "JP1") (pin "7") (pinfunction "7_7") (pintype "passive"))
      (node (ref "JP1") (pin "8") (pinfunction "8_8") (pintype "passive"))
      (node (ref "JP2") (pin "1") (pinfunction "1_1") (pintype "passive"))
      (node (ref "POT_A") (pin "P$3") (pinfunction "A_P$3") (pintype "passive"))
      (node (ref "POT_B") (pin "P$3") (pinfunction "A_P$3") (pintype "passive"))
      (node (ref "POT_C") (pin "P$3") (pinfunction "A_P$3") (pintype "passive"))
      (node (ref "Q1") (pin "2") (pinfunction "LID1_2") (pintype "power_in"))
      (node (ref "Q1") (pin "4") (pinfunction "LID2_4") (pintype "power_in"))
      (node (ref "Q2") (pin "E") (pinfunction "E_E") (pintype "passive"))
      (node (ref "Q3") (pin "E") (pinfunction "E_E") (pintype "passive"))
      (node (ref "Q4") (pin "E") (pinfunction "E_E") (pintype "passive"))
      (node (ref "R20") (pin "1") (pinfunction "1_1") (pintype "passive"))
      (node (ref "R21") (pin "1") (pinfunction "1_1") (pintype "passive"))
      (node (ref "R23") (pin "1") (pinfunction "1_1") (pintype "passive"))
      (node (ref "R45") (pin "2") (pinfunction "2_2") (pintype "passive"))
      (node (ref "R46") (pin "2") (pinfunction "2_2") (pintype "passive"))
      (node (ref "R47") (pin "2") (pinfunction "2_2") (pintype "passive"))
      (node (ref "R48") (pin "2") (pinfunction "2_2") (pintype "passive"))
      (node (ref "R49") (pin "2") (pinfunction "2_2") (pintype "passive"))
      (node (ref "R5") (pin "2") (pinfunction "2_2") (pintype "passive"))
      (node (ref "R50") (pin "2") (pinfunction "2_2") (pintype "passive"))
      (node (ref "SLD_A") (pin "1") (pinfunction "A_1") (pintype "passive"))
      (node (ref "SLD_B") (pin "1") (pinfunction "A_1") (pintype "passive"))
      (node (ref "SLD_C") (pin "1") (pinfunction "A_1") (pintype "passive"))
      (node (ref "SW_A") (pin "1") (pinfunction "1_1") (pintype "passive"))
      (node (ref "SW_A") (pin "2") (pinfunction "2_2") (pintype "passive"))
      (node (ref "SW_B") (pin "1") (pinfunction "1_1") (pintype "passive"))
      (node (ref "SW_B") (pin "2") (pinfunction "2_2") (pintype "passive"))
      (node (ref "SW_C") (pin "1") (pinfunction "1_1") (pintype "passive"))
      (node (ref "SW_C") (pin "2") (pinfunction "2_2") (pintype "passive"))
      (node (ref "U$1") (pin "6") (pinfunction "P$6_6") (pintype "bidirectional"))
      (node (ref "U1") (pin "16") (pinfunction "VSS_2_16") (pintype "power_in"))
      (node (ref "U1") (pin "31") (pinfunction "BOOT0_31") (pintype "input"))
      (node (ref "U1") (pin "32") (pinfunction "VSS_1_32") (pintype "power_in"))
      (node (ref "U2") (pin "10") (pinfunction "+IN_10") (pintype "input"))
      (node (ref "U2") (pin "11") (pinfunction "V-_11") (pintype "power_in"))
      (node (ref "U2") (pin "12") (pinfunction "+IN_12") (pintype "input"))
      (node (ref "U2") (pin "3") (pinfunction "+IN_3") (pintype "input"))
      (node (ref "U2") (pin "5") (pinfunction "+IN_5") (pintype "input"))
      (node (ref "U3") (pin "10") (pinfunction "+IN_10") (pintype "input"))
      (node (ref "U3") (pin "12") (pinfunction "+IN_12") (pintype "input"))
      (node (ref "U3") (pin "3") (pinfunction "+IN_3") (pintype "input"))
      (node (ref "U3") (pin "5") (pinfunction "+IN_5") (pintype "input"))
    )
    (net (code "24") (name "LEDS_SCK") (class "Default")
      (node (ref "IC5") (pin "3") (pinfunction "SCLK_3") (pintype "bidirectional"))
      (node (ref "U1") (pin "26") (pinfunction "PB3_26") (pintype "bidirectional"))
    )
    (net (code "25") (name "LEDS_SIN") (class "Default")
      (node (ref "IC5") (pin "2") (pinfunction "SIN_2") (pintype "bidirectional"))
      (node (ref "U1") (pin "28") (pinfunction "PB5_28") (pintype "bidirectional"))
    )
    (net (code "26") (name "LEDS_SS") (class "Default")
      (node (ref "IC5") (pin "4") (pinfunction "LAT_4") (pintype "bidirectional"))
      (node (ref "U1") (pin "8") (pinfunction "PA2_8") (pintype "bidirectional"))
    )
    (net (code "27") (name "N_U") (class "Default")
      (node (ref "U2") (pin "6") (pinfunction "-IN_6") (pintype "input"))
      (node (ref "U2") (pin "7") (pinfunction "OUT_7") (pintype "output"))
    )
    (net (code "28") (name "Net-(A-GRN)") (class "Default")
      (node (ref "A") (pin "GREEN_C") (pinfunction "GRN_GREEN_C") (pintype "bidirectional"))
      (node (ref "IC5") (pin "9") (pinfunction "OUT4_9") (pintype "bidirectional"))
    )
    (net (code "29") (name "Net-(A-RED)") (class "Default")
      (node (ref "A") (pin "RED_C") (pinfunction "RED_RED_C") (pintype "bidirectional"))
      (node (ref "IC5") (pin "10") (pinfunction "OUT5_10") (pintype "bidirectional"))
    )
    (net (code "30") (name "Net-(B-GRN)") (class "Default")
      (node (ref "B") (pin "GREEN_C") (pinfunction "GRN_GREEN_C") (pintype "bidirectional"))
      (node (ref "IC5") (pin "11") (pinfunction "OUT6_11") (pintype "bidirectional"))
    )
    (net (code "31") (name "Net-(B-RED)") (class "Default")
      (node (ref "B") (pin "RED_C") (pinfunction "RED_RED_C") (pintype "bidirectional"))
      (node (ref "IC5") (pin "12") (pinfunction "OUT7_12") (pintype "bidirectional"))
    )
    (net (code "32") (name "Net-(C-GRN)") (class "Default")
      (node (ref "C") (pin "GREEN_C") (pinfunction "GRN_GREEN_C") (pintype "bidirectional"))
      (node (ref "IC5") (pin "8") (pinfunction "OUT3_8") (pintype "bidirectional"))
    )
    (net (code "33") (name "Net-(C-RED)") (class "Default")
      (node (ref "C") (pin "RED_C") (pinfunction "RED_RED_C") (pintype "bidirectional"))
      (node (ref "IC5") (pin "7") (pinfunction "OUT2_7") (pintype "bidirectional"))
    )
    (net (code "34") (name "Net-(C1-Pad1)") (class "Default")
      (node (ref "C1") (pin "1") (pinfunction "1_1") (pintype "passive"))
      (node (ref "D1") (pin "C") (pinfunction "C_C") (pintype "passive"))
      (node (ref "L1") (pin "1") (pinfunction "1_1") (pintype "passive"))
      (node (ref "L2") (pin "2") (pinfunction "2_2") (pintype "passive"))
      (node (ref "L3") (pin "2") (pinfunction "2_2") (pintype "passive"))
    )
    (net (code "35") (name "Net-(C22-Pad2)") (class "Default")
      (node (ref "C22") (pin "2") (pinfunction "2_2") (pintype "passive"))
      (node (ref "Q1") (pin "1") (pinfunction "1_1") (pintype "passive"))
      (node (ref "R6") (pin "2") (pinfunction "2_2") (pintype "passive"))
    )
    (net (code "36") (name "Net-(D2-PadA)") (class "Default")
      (node (ref "D2") (pin "A") (pinfunction "A_A") (pintype "passive"))
      (node (ref "L4") (pin "2") (pinfunction "2_2") (pintype "passive"))
    )
    (net (code "37") (name "Net-(D3-PadC)") (class "Default")
      (node (ref "D3") (pin "C") (pinfunction "C_C") (pintype "passive"))
      (node (ref "Q2") (pin "B") (pinfunction "B_B") (pintype "passive"))
      (node (ref "R18") (pin "2") (pinfunction "2_2") (pintype "passive"))
      (node (ref "R23") (pin "2") (pinfunction "2_2") (pintype "passive"))
    )
    (net (code "38") (name "Net-(D4-PadC)") (class "Default")
      (node (ref "D4") (pin "C") (pinfunction "C_C") (pintype "passive"))
      (node (ref "Q3") (pin "B") (pinfunction "B_B") (pintype "passive"))
      (node (ref "R19") (pin "2") (pinfunction "2_2") (pintype "passive"))
      (node (ref "R20") (pin "2") (pinfunction "2_2") (pintype "passive"))
    )
    (net (code "39") (name "Net-(D5-PadC)") (class "Default")
      (node (ref "D5") (pin "C") (pinfunction "C_C") (pintype "passive"))
      (node (ref "Q4") (pin "B") (pinfunction "B_B") (pintype "passive"))
      (node (ref "R21") (pin "2") (pinfunction "2_2") (pintype "passive"))
      (node (ref "R22") (pin "2") (pinfunction "2_2") (pintype "passive"))
    )
    (net (code "40") (name "Net-(IC1-VI)") (class "Default")
      (node (ref "C5") (pin "1") (pinfunction "1_1") (pintype "passive"))
      (node (ref "IC1") (pin "1") (pinfunction "VI_1") (pintype "input"))
      (node (ref "L1") (pin "2") (pinfunction "2_2") (pintype "passive"))
    )
    (net (code "41") (name "Net-(IC2-VI)") (class "Default")
      (node (ref "C3") (pin "1") (pinfunction "1_1") (pintype "passive"))
      (node (ref "IC2") (pin "3") (pinfunction "VI_3") (pintype "input"))
      (node (ref "L2") (pin "1") (pinfunction "1_1") (pintype "passive"))
    )
    (net (code "42") (name "Net-(IC4A-X0)") (class "Default")
      (node (ref "IC4") (pin "13") (pinfunction "X0_13") (pintype "bidirectional"))
      (node (ref "POT_C") (pin "P$2") (pinfunction "S_P$2") (pintype "passive"))
    )
    (net (code "43") (name "Net-(IC4A-X1)") (class "Default")
      (node (ref "IC4") (pin "14") (pinfunction "X1_14") (pintype "bidirectional"))
      (node (ref "SLD_C") (pin "2") (pinfunction "S_2") (pintype "passive"))
    )
    (net (code "44") (name "Net-(IC4A-X2)") (class "Default")
      (node (ref "IC4") (pin "15") (pinfunction "X2_15") (pintype "bidirectional"))
      (node (ref "SLD_B") (pin "2") (pinfunction "S_2") (pintype "passive"))
    )
    (net (code "45") (name "Net-(IC4A-X3)") (class "Default")
      (node (ref "IC4") (pin "12") (pinfunction "X3_12") (pintype "bidirectional"))
      (node (ref "POT_A") (pin "P$2") (pinfunction "S_P$2") (pintype "passive"))
    )
    (net (code "46") (name "Net-(IC4A-X4)") (class "Default")
      (node (ref "IC4") (pin "1") (pinfunction "X4_1") (pintype "bidirectional"))
      (node (ref "SLD_A") (pin "2") (pinfunction "S_2") (pintype "passive"))
    )
    (net (code "47") (name "Net-(IC4A-X5)") (class "Default")
      (node (ref "IC4") (pin "5") (pinfunction "X5_5") (pintype "bidirectional"))
      (node (ref "POT_B") (pin "P$2") (pinfunction "S_P$2") (pintype "passive"))
    )
    (net (code "48") (name "Net-(IC5-IREF)") (class "Default")
      (node (ref "IC5") (pin "23") (pinfunction "IREF_23") (pintype "bidirectional"))
      (node (ref "R5") (pin "1") (pinfunction "1_1") (pintype "passive"))
    )
    (net (code "49") (name "Net-(IC5-OUT8)") (class "Default")
      (node (ref "IC5") (pin "13") (pinfunction "OUT8_13") (pintype "bidirectional"))
      (node (ref "R16") (pin "2") (pinfunction "2_2") (pintype "passive"))
    )
    (net (code "50") (name "Net-(IC5-OUT9)") (class "Default")
      (node (ref "IC5") (pin "14") (pinfunction "OUT9_14") (pintype "bidirectional"))
      (node (ref "R17") (pin "2") (pinfunction "2_2") (pintype "passive"))
    )
    (net (code "51") (name "Net-(IC5-OUT10)") (class "Default")
      (node (ref "IC5") (pin "15") (pinfunction "OUT10_15") (pintype "bidirectional"))
      (node (ref "R15") (pin "2") (pinfunction "2_2") (pintype "passive"))
    )
    (net (code "52") (name "Net-(IC5-VCC)") (class "Default")
      (node (ref "C14") (pin "1") (pinfunction "1_1") (pintype "passive"))
      (node (ref "C15") (pin "1") (pinfunction "1_1") (pintype "passive"))
      (node (ref "IC5") (pin "24") (pinfunction "VCC_24") (pintype "bidirectional"))
      (node (ref "L5") (pin "1") (pinfunction "1_1") (pintype "passive"))
    )
    (net (code "53") (name "Net-(IC6A-+IN)") (class "Default")
      (node (ref "IC6") (pin "3") (pinfunction "+IN_3") (pintype "input"))
      (node (ref "R44") (pin "2") (pinfunction "2_2") (pintype "passive"))
      (node (ref "R47") (pin "1") (pinfunction "1_1") (pintype "passive"))
    )
    (net (code "54") (name "Net-(IC6A--IN)") (class "Default")
      (node (ref "IC6") (pin "2") (pinfunction "-IN_2") (pintype "input"))
      (node (ref "R13") (pin "1") (pinfunction "1_1") (pintype "passive"))
    )
    (net (code "55") (name "Net-(IC6A-OUT)") (class "Default")
      (node (ref "IC6") (pin "1") (pinfunction "OUT_1") (pintype "output"))
      (node (ref "R39") (pin "2") (pinfunction "2_2") (pintype "passive"))
      (node (ref "R44") (pin "1") (pinfunction "1_1") (pintype "passive"))
    )
    (net (code "56") (name "Net-(IC6B-+IN)") (class "Default")
      (node (ref "IC6") (pin "5") (pinfunction "+IN_5") (pintype "input"))
      (node (ref "R41") (pin "2") (pinfunction "2_2") (pintype "passive"))
      (node (ref "R46") (pin "1") (pinfunction "1_1") (pintype "passive"))
    )
    (net (code "57") (name "Net-(IC6B--IN)") (class "Default")
      (node (ref "IC6") (pin "6") (pinfunction "-IN_6") (pintype "input"))
      (node (ref "R12") (pin "1") (pinfunction "1_1") (pintype "passive"))
    )
    (net (code "58") (name "Net-(IC6B-OUT)") (class "Default")
      (node (ref "IC6") (pin "7") (pinfunction "OUT_7") (pintype "output"))
      (node (ref "R38") (pin "2") (pinfunction "2_2") (pintype "passive"))
      (node (ref "R41") (pin "1") (pinfunction "1_1") (pintype "passive"))
    )
    (net (code "59") (name "Net-(IC6C-+IN)") (class "Default")
      (node (ref "IC6") (pin "10") (pinfunction "+IN_10") (pintype "input"))
      (node (ref "R36") (pin "2") (pinfunction "2_2") (pintype "passive"))
      (node (ref "R45") (pin "1") (pinfunction "1_1") (pintype "passive"))
    )
    (net (code "60") (name "Net-(IC6C--IN)") (class "Default")
      (node (ref "IC6") (pin "9") (pinfunction "-IN_9") (pintype "input"))
      (node (ref "R11") (pin "1") (pinfunction "1_1") (pintype "passive"))
    )
    (net (code "61") (name "Net-(IC6C-OUT)") (class "Default")
      (node (ref "IC6") (pin "8") (pinfunction "OUT_8") (pintype "output"))
      (node (ref "R36") (pin "1") (pinfunction "1_1") (pintype "passive"))
      (node (ref "R37") (pin "2") (pinfunction "2_2") (pintype "passive"))
    )
    (net (code "62") (name "Net-(IC6D--IN)") (class "Default")
      (node (ref "IC6") (pin "13") (pinfunction "-IN_13") (pintype "input"))
      (node (ref "IC6") (pin "14") (pinfunction "OUT_14") (pintype "output"))
    )
    (net (code "63") (name "Net-(IC14A-+IN)") (class "Default")
      (node (ref "IC14") (pin "3") (pinfunction "+IN_3") (pintype "input"))
      (node (ref "LED3") (pin "2") (pinfunction "2_2") (pintype "bidirectional"))
      (node (ref "R48") (pin "1") (pinfunction "1_1") (pintype "passive"))
    )
    (net (code "64") (name "Net-(IC14A--IN)") (class "Default")
      (node (ref "C33") (pin "2") (pinfunction "2_2") (pintype "passive"))
      (node (ref "IC14") (pin "2") (pinfunction "-IN_2") (pintype "input"))
      (node (ref "R43") (pin "2") (pinfunction "2_2") (pintype "passive"))
      (node (ref "U3") (pin "1") (pinfunction "OUT_1") (pintype "output"))
    )
    (net (code "65") (name "Net-(IC14A-OUT)") (class "Default")
      (node (ref "IC14") (pin "1") (pinfunction "OUT_1") (pintype "output"))
      (node (ref "LED3") (pin "1") (pinfunction "1_1") (pintype "bidirectional"))
    )
    (net (code "66") (name "Net-(IC14B-+IN)") (class "Default")
      (node (ref "C32") (pin "2") (pinfunction "2_2") (pintype "passive"))
      (node (ref "IC14") (pin "5") (pinfunction "+IN_5") (pintype "input"))
      (node (ref "R42") (pin "2") (pinfunction "2_2") (pintype "passive"))
      (node (ref "U3") (pin "7") (pinfunction "OUT_7") (pintype "output"))
    )
    (net (code "67") (name "Net-(IC14B--IN)") (class "Default")
      (node (ref "IC14") (pin "6") (pinfunction "-IN_6") (pintype "input"))
      (node (ref "LED1") (pin "2") (pinfunction "2_2") (pintype "bidirectional"))
      (node (ref "R49") (pin "1") (pinfunction "1_1") (pintype "passive"))
    )
    (net (code "68") (name "Net-(IC14B-OUT)") (class "Default")
      (node (ref "IC14") (pin "7") (pinfunction "OUT_7") (pintype "output"))
      (node (ref "LED1") (pin "1") (pinfunction "1_1") (pintype "bidirectional"))
    )
    (net (code "69") (name "Net-(IC14C-+IN)") (class "Default")
      (node (ref "IC14") (pin "10") (pinfunction "+IN_10") (pintype "input"))
      (node (ref "LED2") (pin "2") (pinfunction "2_2") (pintype "bidirectional"))
      (node (ref "R50") (pin "1") (pinfunction "1_1") (pintype "passive"))
    )
    (net (code "70") (name "Net-(IC14C--IN)") (class "Default")
      (node (ref "C34") (pin "2") (pinfunction "2_2") (pintype "passive"))
      (node (ref "IC14") (pin "9") (pinfunction "-IN_9") (pintype "input"))
      (node (ref "R40") (pin "2") (pinfunction "2_2") (pintype "passive"))
      (node (ref "U3") (pin "8") (pinfunction "OUT_8") (pintype "output"))
    )
    (net (code "71") (name "Net-(IC14C-OUT)") (class "Default")
      (node (ref "IC14") (pin "8") (pinfunction "OUT_8") (pintype "output"))
      (node (ref "LED2") (pin "1") (pinfunction "1_1") (pintype "bidirectional"))
    )
    (net (code "72") (name "Net-(IC14D-+IN)") (class "Default")
      (node (ref "IC14") (pin "12") (pinfunction "+IN_12") (pintype "input"))
      (node (ref "IC14") (pin "14") (pinfunction "OUT_14") (pintype "output"))
    )
    (net (code "73") (name "Net-(J4-3)") (class "Default")
      (node (ref "J4") (pin "P3") (pinfunction "3_P3") (pintype "passive"))
      (node (ref "R24") (pin "2") (pinfunction "2_2") (pintype "passive"))
    )
    (net (code "74") (name "Net-(J6-3)") (class "Default")
      (node (ref "J6") (pin "P3") (pinfunction "3_P3") (pintype "passive"))
      (node (ref "R26") (pin "2") (pinfunction "2_2") (pintype "passive"))
    )
    (net (code "75") (name "Net-(J7-3)") (class "Default")
      (node (ref "J7") (pin "P3") (pinfunction "3_P3") (pintype "passive"))
      (node (ref "R37") (pin "1") (pinfunction "1_1") (pintype "passive"))
    )
    (net (code "76") (name "Net-(J8-3)") (class "Default")
      (node (ref "J8") (pin "P3") (pinfunction "3_P3") (pintype "passive"))
      (node (ref "R38") (pin "1") (pinfunction "1_1") (pintype "passive"))
    )
    (net (code "77") (name "Net-(J9-3)") (class "Default")
      (node (ref "J9") (pin "P3") (pinfunction "3_P3") (pintype "passive"))
      (node (ref "R39") (pin "1") (pinfunction "1_1") (pintype "passive"))
    )
    (net (code "78") (name "Net-(J10-3)") (class "Default")
      (node (ref "J10") (pin "P3") (pinfunction "3_P3") (pintype "passive"))
      (node (ref "R35") (pin "1") (pinfunction "1_1") (pintype "passive"))
      (node (ref "R40") (pin "1") (pinfunction "1_1") (pintype "passive"))
    )
    (net (code "79") (name "Net-(J11-3)") (class "Default")
      (node (ref "J11") (pin "P3") (pinfunction "3_P3") (pintype "passive"))
      (node (ref "R29") (pin "1") (pinfunction "1_1") (pintype "passive"))
      (node (ref "R42") (pin "1") (pinfunction "1_1") (pintype "passive"))
    )
    (net (code "80") (name "Net-(J12-3)") (class "Default")
      (node (ref "J12") (pin "P3") (pinfunction "3_P3") (pintype "passive"))
      (node (ref "R32") (pin "1") (pinfunction "1_1") (pintype "passive"))
      (node (ref "R43") (pin "1") (pinfunction "1_1") (pintype "passive"))
    )
    (net (code "81") (name "Net-(Q1B-2)") (class "Default")
      (node (ref "C21") (pin "2") (pinfunction "2_2") (pintype "passive"))
      (node (ref "Q1") (pin "3") (pinfunction "2_3") (pintype "passive"))
      (node (ref "R9") (pin "2") (pinfunction "2_2") (pintype "passive"))
    )
    (net (code "82") (name "Net-(SLD_AA-A)") (class "Default")
      (node (ref "SLD_A") (pin "B") (pinfunction "A_B") (pintype "passive"))
      (node (ref "SLD_B") (pin "B") (pinfunction "A_B") (pintype "passive"))
      (node (ref "SLD_C") (pin "B") (pinfunction "A_B") (pintype "passive"))
    )
    (net (code "83") (name "Net-(SLD_AA-C)") (class "Default")
      (node (ref "R16") (pin "1") (pinfunction "1_1") (pintype "passive"))
      (node (ref "SLD_A") (pin "E") (pinfunction "C_E") (pintype "passive"))
    )
    (net (code "84") (name "Net-(SLD_BA-C)") (class "Default")
      (node (ref "R17") (pin "1") (pinfunction "1_1") (pintype "passive"))
      (node (ref "SLD_B") (pin "E") (pinfunction "C_E") (pintype "passive"))
    )
    (net (code "85") (name "Net-(SLD_CA-C)") (class "Default")
      (node (ref "R15") (pin "1") (pinfunction "1_1") (pintype "passive"))
      (node (ref "SLD_C") (pin "E") (pinfunction "C_E") (pintype "passive"))
    )
    (net (code "86") (name "Net-(U1-PF0{slash}OSC_IN)") (class "Default")
      (node (ref "R9") (pin "1") (pinfunction "1_1") (pintype "passive"))
      (node (ref "U1") (pin "2") (pinfunction "PF0/OSC_IN_2") (pintype "bidirectional"))
    )
    (net (code "87") (name "Net-(U1-PF1{slash}OSC_OUT)") (class "Default")
      (node (ref "R6") (pin "1") (pinfunction "1_1") (pintype "passive"))
      (node (ref "U1") (pin "3") (pinfunction "PF1/OSC_OUT_3") (pintype "bidirectional"))
    )
    (net (code "88") (name "Net-(U2A--IN)") (class "Default")
      (node (ref "C30") (pin "1") (pinfunction "1_1") (pintype "passive"))
      (node (ref "R14") (pin "2") (pinfunction "2_2") (pintype "passive"))
      (node (ref "R2") (pin "1") (pinfunction "1_1") (pintype "passive"))
      (node (ref "R26") (pin "1") (pinfunction "1_1") (pintype "passive"))
      (node (ref "U2") (pin "2") (pinfunction "-IN_2") (pintype "input"))
    )
    (net (code "89") (name "Net-(U2C--IN)") (class "Default")
      (node (ref "C23") (pin "1") (pinfunction "1_1") (pintype "passive"))
      (node (ref "R25") (pin "1") (pinfunction "1_1") (pintype "passive"))
      (node (ref "R3") (pin "1") (pinfunction "1_1") (pintype "passive"))
      (node (ref "R7") (pin "2") (pinfunction "2_2") (pintype "passive"))
      (node (ref "U2") (pin "9") (pinfunction "-IN_9") (pintype "input"))
    )
    (net (code "90") (name "Net-(U2D--IN)") (class "Default")
      (node (ref "C24") (pin "1") (pinfunction "1_1") (pintype "passive"))
      (node (ref "R24") (pin "1") (pinfunction "1_1") (pintype "passive"))
      (node (ref "R4") (pin "1") (pinfunction "1_1") (pintype "passive"))
      (node (ref "R8") (pin "2") (pinfunction "2_2") (pintype "passive"))
      (node (ref "U2") (pin "13") (pinfunction "-IN_13") (pintype "input"))
    )
    (net (code "91") (name "Net-(U3A--IN)") (class "Default")
      (node (ref "C33") (pin "1") (pinfunction "1_1") (pintype "passive"))
      (node (ref "R30") (pin "1") (pinfunction "1_1") (pintype "passive"))
      (node (ref "R31") (pin "1") (pinfunction "1_1") (pintype "passive"))
      (node (ref "R32") (pin "2") (pinfunction "2_2") (pintype "passive"))
      (node (ref "U3") (pin "2") (pinfunction "-IN_2") (pintype "input"))
    )
    (net (code "92") (name "Net-(U3B--IN)") (class "Default")
      (node (ref "C32") (pin "1") (pinfunction "1_1") (pintype "passive"))
      (node (ref "R27") (pin "1") (pinfunction "1_1") (pintype "passive"))
      (node (ref "R28") (pin "1") (pinfunction "1_1") (pintype "passive"))
      (node (ref "R29") (pin "2") (pinfunction "2_2") (pintype "passive"))
      (node (ref "U3") (pin "6") (pinfunction "-IN_6") (pintype "input"))
    )
    (net (code "93") (name "Net-(U3C--IN)") (class "Default")
      (node (ref "C34") (pin "1") (pinfunction "1_1") (pintype "passive"))
      (node (ref "R33") (pin "1") (pinfunction "1_1") (pintype "passive"))
      (node (ref "R34") (pin "1") (pinfunction "1_1") (pintype "passive"))
      (node (ref "R35") (pin "2") (pinfunction "2_2") (pintype "passive"))
      (node (ref "U3") (pin "9") (pinfunction "-IN_9") (pintype "input"))
    )
    (net (code "94") (name "Net-(U3D--IN)") (class "Default")
      (node (ref "U3") (pin "13") (pinfunction "-IN_13") (pintype "input"))
      (node (ref "U3") (pin "14") (pinfunction "OUT_14") (pintype "output"))
    )
    (net (code "95") (name "POTS_ADDR_A") (class "Default")
      (node (ref "IC4") (pin "11") (pinfunction "A_11") (pintype "input"))
      (node (ref "U1") (pin "13") (pinfunction "PA7_13") (pintype "bidirectional"))
    )
    (net (code "96") (name "POTS_ADDR_B") (class "Default")
      (node (ref "IC4") (pin "10") (pinfunction "B_10") (pintype "input"))
      (node (ref "U1") (pin "18") (pinfunction "PA8_18") (pintype "bidirectional"))
    )
    (net (code "97") (name "POTS_ADDR_C") (class "Default")
      (node (ref "IC4") (pin "9") (pinfunction "C_9") (pintype "input"))
      (node (ref "U1") (pin "19") (pinfunction "PA9_19") (pintype "bidirectional"))
    )
    (net (code "98") (name "RESET") (class "Default")
      (node (ref "C28") (pin "1") (pinfunction "1_1") (pintype "passive"))
      (node (ref "JP2") (pin "4") (pinfunction "4_4") (pintype "passive"))
      (node (ref "R10") (pin "2") (pinfunction "2_2") (pintype "passive"))
      (node (ref "U1") (pin "4") (pinfunction "NRST_4") (pintype "bidirectional"))
    )
    (net (code "99") (name "SWCLK") (class "Default")
      (node (ref "JP2") (pin "3") (pinfunction "3_3") (pintype "passive"))
      (node (ref "U1") (pin "24") (pinfunction "PA14_24") (pintype "bidirectional"))
    )
    (net (code "100") (name "SWDIO") (class "Default")
      (node (ref "JP2") (pin "2") (pinfunction "2_2") (pintype "passive"))
      (node (ref "U1") (pin "23") (pinfunction "PA13_23") (pintype "bidirectional"))
    )
    (net (code "101") (name "SW_MODE_A") (class "Default")
      (node (ref "SW_A") (pin "3") (pinfunction "3_3") (pintype "passive"))
      (node (ref "SW_A") (pin "4") (pinfunction "4_4") (pintype "passive"))
      (node (ref "U1") (pin "27") (pinfunction "PB4_27") (pintype "bidirectional"))
    )
    (net (code "102") (name "SW_MODE_B") (class "Default")
      (node (ref "SW_B") (pin "3") (pinfunction "3_3") (pintype "passive"))
      (node (ref "SW_B") (pin "4") (pinfunction "4_4") (pintype "passive"))
      (node (ref "U1") (pin "29") (pinfunction "PB6_29") (pintype "bidirectional"))
    )
    (net (code "103") (name "SW_MODE_C") (class "Default")
      (node (ref "SW_C") (pin "3") (pinfunction "3_3") (pintype "passive"))
      (node (ref "SW_C") (pin "4") (pinfunction "4_4") (pintype "passive"))
      (node (ref "U1") (pin "30") (pinfunction "PB7_30") (pintype "bidirectional"))
    )
    (net (code "104") (name "VCC") (class "Default")
      (node (ref "C2") (pin "1") (pinfunction "1_1") (pintype "passive"))
      (node (ref "C31") (pin "1") (pinfunction "1_1") (pintype "passive"))
      (node (ref "C35") (pin "1") (pinfunction "1_1") (pintype "passive"))
      (node (ref "C36") (pin "1") (pinfunction "1_1") (pintype "passive"))
      (node (ref "C4") (pin "1") (pinfunction "1_1") (pintype "passive"))
      (node (ref "IC14") (pin "4") (pinfunction "V+_4") (pintype "power_in"))
      (node (ref "IC6") (pin "4") (pinfunction "V+_4") (pintype "power_in"))
      (node (ref "L3") (pin "1") (pinfunction "1_1") (pintype "passive"))
      (node (ref "U$1") (pin "1") (pinfunction "P$1_1") (pintype "bidirectional"))
      (node (ref "U3") (pin "4") (pinfunction "V+_4") (pintype "power_in"))
    )
    (net (code "105") (name "VEE") (class "Default")
      (node (ref "C10") (pin "2") (pinfunction "2_2") (pintype "passive"))
      (node (ref "C25") (pin "2") (pinfunction "2_2") (pintype "passive"))
      (node (ref "C37") (pin "2") (pinfunction "2_2") (pintype "passive"))
      (node (ref "C9") (pin "2") (pinfunction "2_2") (pintype "passive"))
      (node (ref "IC14") (pin "11") (pinfunction "V-_11") (pintype "power_in"))
      (node (ref "L4") (pin "1") (pinfunction "1_1") (pintype "passive"))
      (node (ref "R1") (pin "1") (pinfunction "1_1") (pintype "passive"))
      (node (ref "U$1") (pin "2") (pinfunction "P$2_2") (pintype "bidirectional"))
      (node (ref "U3") (pin "11") (pinfunction "V-_11") (pintype "power_in"))
    )
    (net (code "106") (name "unconnected-(IC4A-X7-Pad4)") (class "Default")
      (node (ref "IC4") (pin "4") (pinfunction "X7_4") (pintype "bidirectional"))
    )
    (net (code "107") (name "unconnected-(IC5-OUT0-Pad5)") (class "Default")
      (node (ref "IC5") (pin "5") (pinfunction "OUT0_5") (pintype "bidirectional"))
    )
    (net (code "108") (name "unconnected-(IC5-OUT1-Pad6)") (class "Default")
      (node (ref "IC5") (pin "6") (pinfunction "OUT1_6") (pintype "bidirectional"))
    )
    (net (code "109") (name "unconnected-(IC5-OUT11-Pad16)") (class "Default")
      (node (ref "IC5") (pin "16") (pinfunction "OUT11_16") (pintype "bidirectional"))
    )
    (net (code "110") (name "unconnected-(IC5-OUT12-Pad17)") (class "Default")
      (node (ref "IC5") (pin "17") (pinfunction "OUT12_17") (pintype "bidirectional"))
    )
    (net (code "111") (name "unconnected-(IC5-OUT13-Pad18)") (class "Default")
      (node (ref "IC5") (pin "18") (pinfunction "OUT13_18") (pintype "bidirectional"))
    )
    (net (code "112") (name "unconnected-(IC5-OUT14-Pad19)") (class "Default")
      (node (ref "IC5") (pin "19") (pinfunction "OUT14_19") (pintype "bidirectional"))
    )
    (net (code "113") (name "unconnected-(IC5-OUT15-Pad20)") (class "Default")
      (node (ref "IC5") (pin "20") (pinfunction "OUT15_20") (pintype "bidirectional"))
    )
    (net (code "114") (name "unconnected-(IC5-SOUT-Pad22)") (class "Default")
      (node (ref "IC5") (pin "22") (pinfunction "SOUT_22") (pintype "bidirectional"))
    )
    (net (code "115") (name "unconnected-(J7-2-PadP2)") (class "Default")
      (node (ref "J7") (pin "P2") (pinfunction "2_P2") (pintype "passive"))
    )
    (net (code "116") (name "unconnected-(J8-2-PadP2)") (class "Default")
      (node (ref "J8") (pin "P2") (pinfunction "2_P2") (pintype "passive"))
    )
    (net (code "117") (name "unconnected-(J9-2-PadP2)") (class "Default")
      (node (ref "J9") (pin "P2") (pinfunction "2_P2") (pintype "passive"))
    )
    (net (code "118") (name "unconnected-(J10-2-PadP2)") (class "Default")
      (node (ref "J10") (pin "P2") (pinfunction "2_P2") (pintype "passive"))
    )
    (net (code "119") (name "unconnected-(J11-2-PadP2)") (class "Default")
      (node (ref "J11") (pin "P2") (pinfunction "2_P2") (pintype "passive"))
    )
    (net (code "120") (name "unconnected-(J12-2-PadP2)") (class "Default")
      (node (ref "J12") (pin "P2") (pinfunction "2_P2") (pintype "passive"))
    )
  )
)
